# mpu-6050.net
KiCad netlist of a schematic drawn in EAGLE
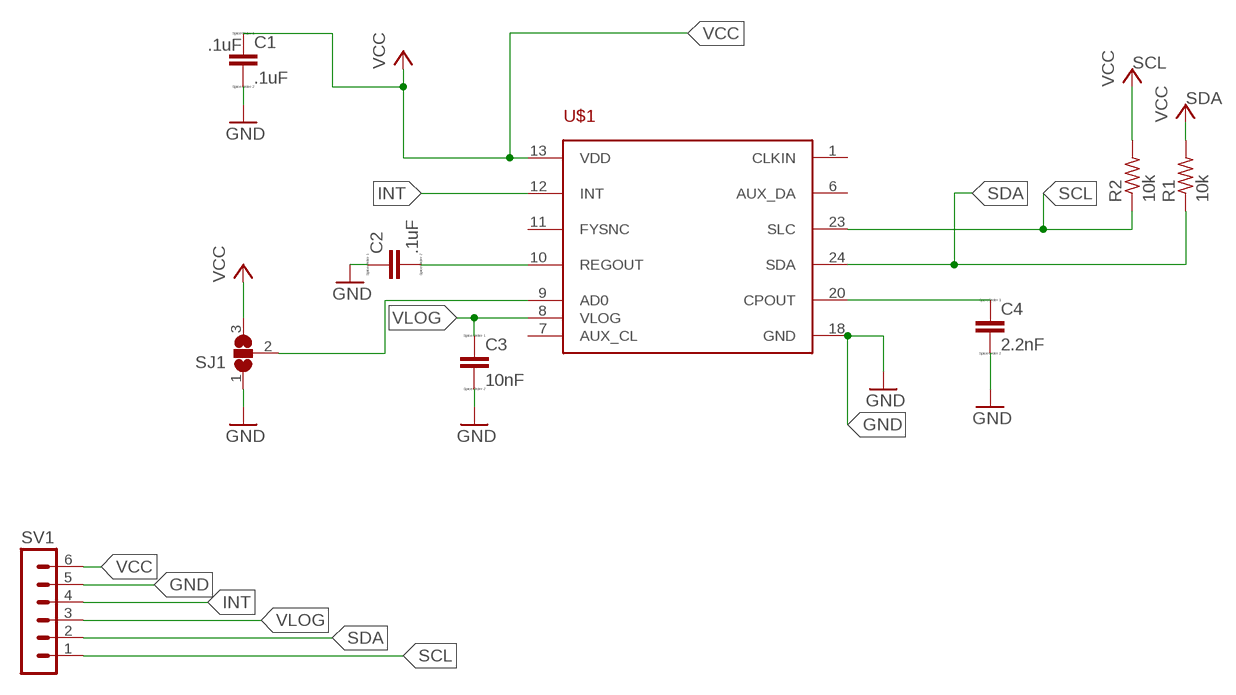
[diagram p0: schematic, sheet 1]

(export (version "E")
  (design (tool "Eeschema 10.0.6"))
  (components
    (comp (ref "C1")
      (value ".1uF")
      (footprint "eagle-import:C0402")
      (fields (field (name "SPICEPREFIX") "C") (field (name "SPICEPREFIX_1") ".1uF"))
      (libsource (lib "eagle-import") (part "CC0402"))
    )
    (comp (ref "C2")
      (value ".1uF")
      (footprint "eagle-import:C0402")
      (libsource (lib "eagle-import") (part "CC0402"))
    )
    (comp (ref "C3")
      (value "10nF")
      (footprint "eagle-import:C0402")
      (libsource (lib "eagle-import") (part "CC0402"))
    )
    (comp (ref "C4")
      (value "2.2nF")
      (footprint "eagle-import:C0402")
      (libsource (lib "eagle-import") (part "CC0402"))
    )
    (comp (ref "R1")
      (value "10k")
      (footprint "eagle-import:R0603")
      (fields (field (name "R2") "10k"))
      (libsource (lib "eagle-import") (part "R-US_R0603"))
    )
    (comp (ref "R2")
      (value "10k")
      (footprint "eagle-import:R0603")
      (libsource (lib "eagle-import") (part "R-US_R0603"))
    )
    (comp (ref "SJ1")
      (value "SJ2W")
      (footprint "eagle-import:SJ_2")
      (libsource (lib "eagle-import") (part "SJ2W"))
    )
    (comp (ref "SV1")
      (value "MA06-1")
      (footprint "eagle-import:MA06-1")
      (libsource (lib "eagle-import") (part "MA06-1"))
    )
    (comp (ref "U$1")
      (value "MPU-6050")
      (footprint "eagle-import:QFN24-4X4")
      (libsource (lib "eagle-import") (part "MPU-6050"))
    )
  )
  (nets
    (net (code "1") (name "GND") (class "Default")
      (node (ref "C1") (pin "2") (pinfunction "2_2") (pintype "passive"))
      (node (ref "C2") (pin "1") (pinfunction "1_1") (pintype "passive"))
      (node (ref "C3") (pin "2") (pinfunction "2_2") (pintype "passive"))
      (node (ref "C4") (pin "2") (pinfunction "2_2") (pintype "passive"))
      (node (ref "SJ1") (pin "1") (pinfunction "1_1") (pintype "passive"))
      (node (ref "SV1") (pin "5") (pinfunction "5_5") (pintype "passive"))
      (node (ref "U$1") (pin "18") (pinfunction "GND_18") (pintype "bidirectional"))
    )
    (net (code "2") (name "INT") (class "Default")
      (node (ref "SV1") (pin "4") (pinfunction "4_4") (pintype "passive"))
      (node (ref "U$1") (pin "12") (pinfunction "INT_12") (pintype "bidirectional"))
    )
    (net (code "3") (name "Net-(U$1-AD0)") (class "Default")
      (node (ref "SJ1") (pin "2") (pinfunction "2_2") (pintype "passive"))
      (node (ref "U$1") (pin "9") (pinfunction "AD0_9") (pintype "bidirectional"))
    )
    (net (code "4") (name "Net-(U$1-CPOUT)") (class "Default")
      (node (ref "C4") (pin "1") (pinfunction "1_1") (pintype "passive"))
      (node (ref "U$1") (pin "20") (pinfunction "CPOUT_20") (pintype "bidirectional"))
    )
    (net (code "5") (name "Net-(U$1-REGOUT)") (class "Default")
      (node (ref "C2") (pin "2") (pinfunction "2_2") (pintype "passive"))
      (node (ref "U$1") (pin "10") (pinfunction "REGOUT_10") (pintype "bidirectional"))
    )
    (net (code "6") (name "SCL") (class "Default")
      (node (ref "R2") (pin "1") (pinfunction "1_1") (pintype "passive"))
      (node (ref "SV1") (pin "1") (pinfunction "1_1") (pintype "passive"))
      (node (ref "U$1") (pin "23") (pinfunction "SLC_23") (pintype "bidirectional"))
    )
    (net (code "7") (name "SDA") (class "Default")
      (node (ref "R1") (pin "1") (pinfunction "1_1") (pintype "passive"))
      (node (ref "SV1") (pin "2") (pinfunction "2_2") (pintype "passive"))
      (node (ref "U$1") (pin "24") (pinfunction "SDA_24") (pintype "bidirectional"))
    )
    (net (code "8") (name "VCC") (class "Default")
      (node (ref "C1") (pin "1") (pinfunction "1_1") (pintype "passive"))
      (node (ref "R1") (pin "2") (pinfunction "2_2") (pintype "passive"))
      (node (ref "R2") (pin "2") (pinfunction "2_2") (pintype "passive"))
      (node (ref "SJ1") (pin "3") (pinfunction "3_3") (pintype "passive"))
      (node (ref "SV1") (pin "6") (pinfunction "6_6") (pintype "passive"))
      (node (ref "U$1") (pin "13") (pinfunction "VDD_13") (pintype "bidirectional"))
    )
    (net (code "9") (name "VLOG") (class "Default")
      (node (ref "C3") (pin "1") (pinfunction "1_1") (pintype "passive"))
      (node (ref "SV1") (pin "3") (pinfunction "3_3") (pintype "passive"))
      (node (ref "U$1") (pin "8") (pinfunction "VLOG_8") (pintype "bidirectional"))
    )
    (net (code "10") (name "unconnected-(U$1-AUX_CL-Pad7)") (class "Default")
      (node (ref "U$1") (pin "7") (pinfunction "AUX_CL_7") (pintype "bidirectional"))
    )
    (net (code "11") (name "unconnected-(U$1-AUX_DA-Pad6)") (class "Default")
      (node (ref "U$1") (pin "6") (pinfunction "AUX_DA_6") (pintype "bidirectional"))
    )
    (net (code "12") (name "unconnected-(U$1-CLKIN-Pad1)") (class "Default")
      (node (ref "U$1") (pin "1") (pinfunction "CLKIN_1") (pintype "bidirectional"))
    )
    (net (code "13") (name "unconnected-(U$1-FYSNC-Pad11)") (class "Default")
      (node (ref "U$1") (pin "11") (pinfunction "FYSNC_11") (pintype "bidirectional"))
    )
  )
)
